# i2c_adc_1.net
KiCad netlist of a schematic drawn in EAGLE
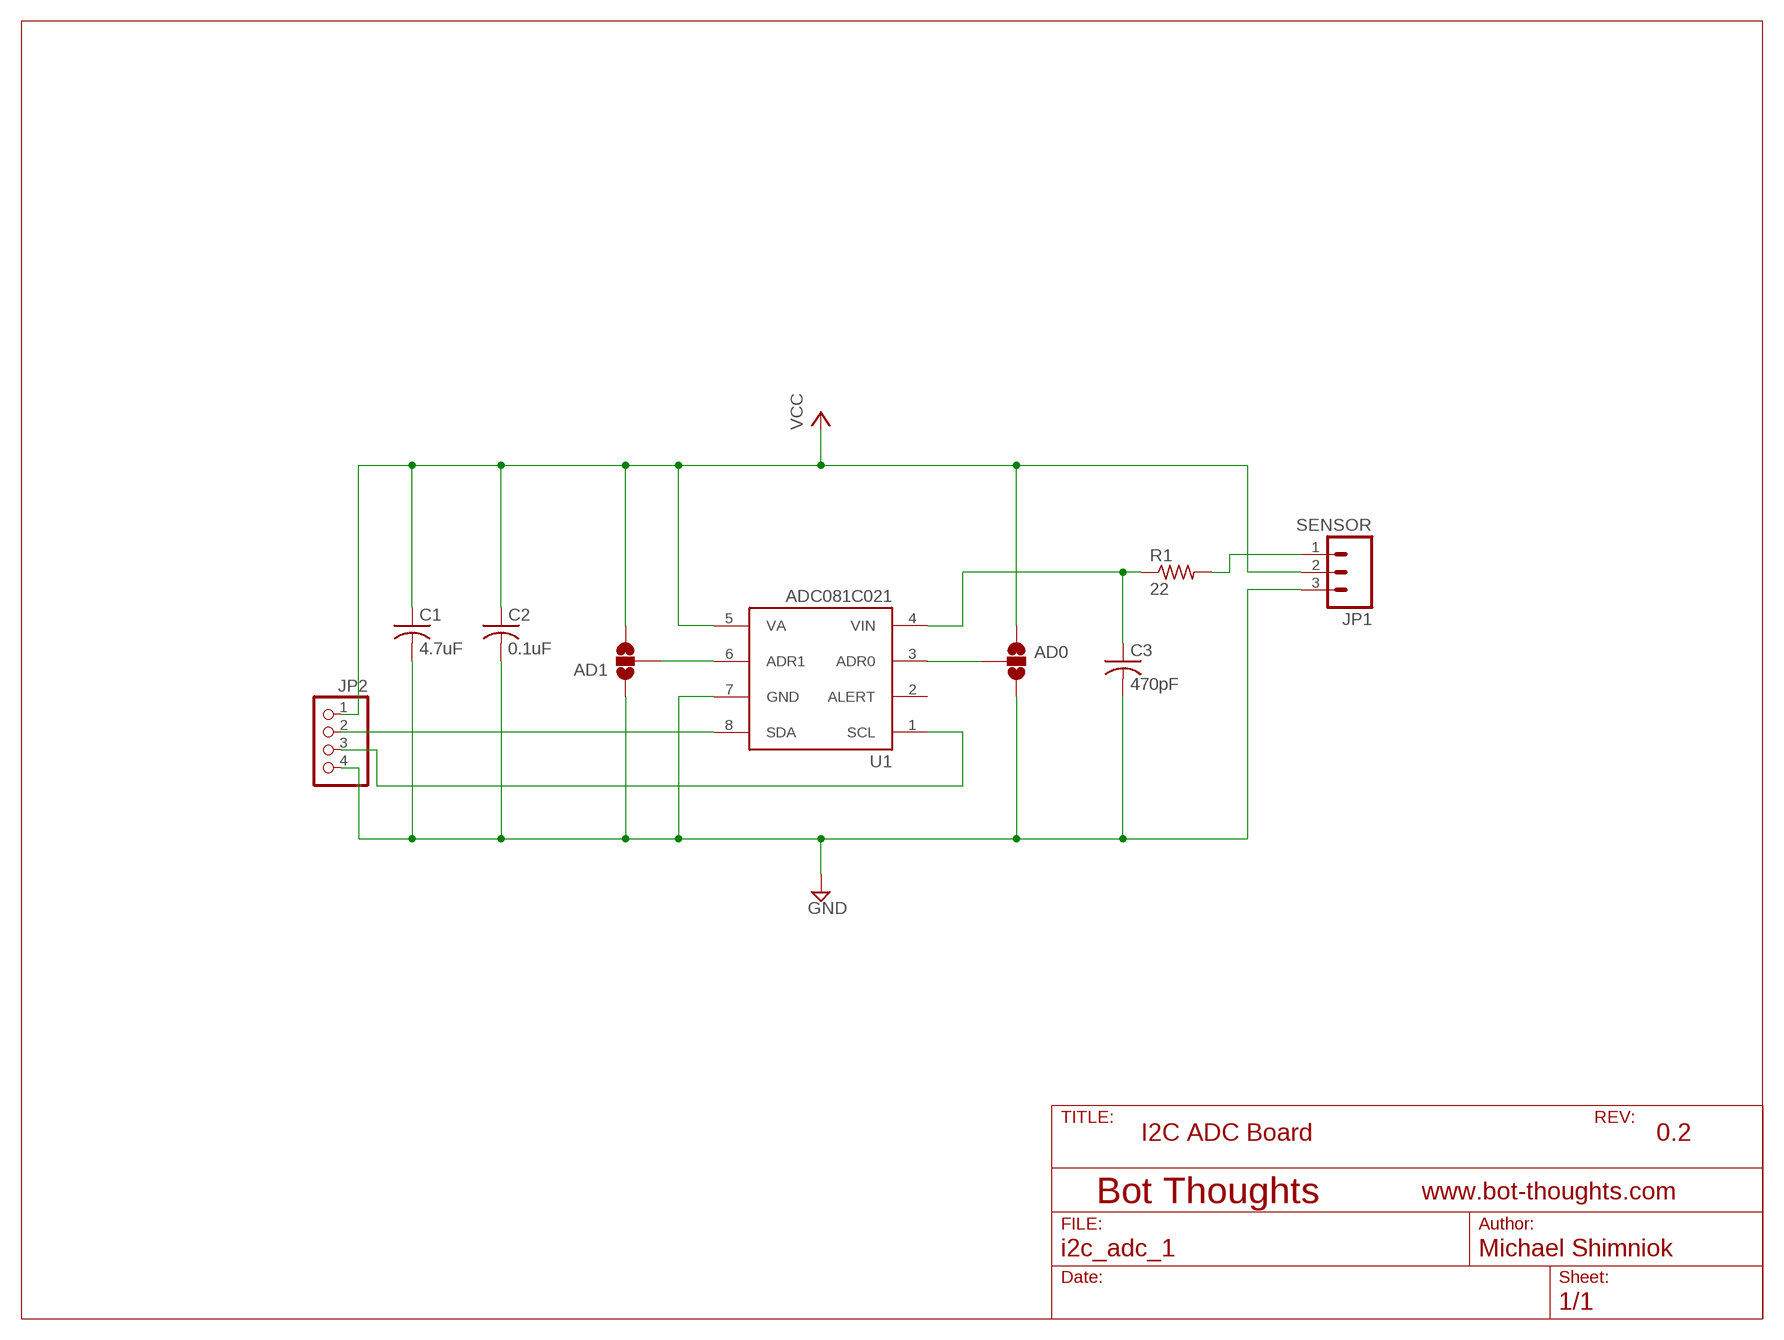
[diagram p0: schematic, sheet 1]

(export (version "E")
  (design (tool "Eeschema 10.0.6"))
  (components
    (comp (ref "AD0")
      (value "SOLDERJUMPER_2WAYS")
      (footprint "eagle-import:SJ_3")
      (libsource (lib "eagle-import") (part "SOLDERJUMPER_2WAYS"))
    )
    (comp (ref "AD1")
      (value "SOLDERJUMPER_2WAYS")
      (footprint "eagle-import:SJ_3")
      (libsource (lib "eagle-import") (part "SOLDERJUMPER_2WAYS"))
    )
    (comp (ref "C1")
      (value "4.7uF")
      (footprint "eagle-import:C0603")
      (libsource (lib "eagle-import") (part "C-USC0603"))
    )
    (comp (ref "C2")
      (value "0.1uF")
      (footprint "eagle-import:C0603")
      (libsource (lib "eagle-import") (part "C-USC0603"))
    )
    (comp (ref "C3")
      (value "470pF")
      (footprint "eagle-import:C0603")
      (libsource (lib "eagle-import") (part "C-USC0603"))
    )
    (comp (ref "JP1")
      (value "SENSOR")
      (footprint "eagle-import:1X03")
      (libsource (lib "eagle-import") (part "M03PTH"))
    )
    (comp (ref "JP2")
      (value "PINHD-1X04_2.54-S")
      (footprint "eagle-import:1X04-S")
      (libsource (lib "eagle-import") (part "PINHD-1X04_2.54-S"))
    )
    (comp (ref "R1")
      (value "22")
      (footprint "eagle-import:R0603")
      (libsource (lib "eagle-import") (part "R-US_R0603"))
    )
    (comp (ref "U1")
      (value "ADC081C021")
      (footprint "eagle-import:MSOP8_0.65")
      (libsource (lib "eagle-import") (part "ADC081C021"))
    )
  )
  (nets
    (net (code "1") (name "GND") (class "Default")
      (node (ref "AD0") (pin "3") (pinfunction "3_3") (pintype "passive"))
      (node (ref "AD1") (pin "1") (pinfunction "1_1") (pintype "passive"))
      (node (ref "C1") (pin "2") (pinfunction "2_2") (pintype "passive"))
      (node (ref "C2") (pin "2") (pinfunction "2_2") (pintype "passive"))
      (node (ref "C3") (pin "2") (pinfunction "2_2") (pintype "passive"))
      (node (ref "JP1") (pin "3") (pinfunction "3_3") (pintype "passive"))
      (node (ref "JP2") (pin "4") (pinfunction "4_4") (pintype "passive"))
      (node (ref "U1") (pin "7") (pinfunction "GND_7") (pintype "bidirectional"))
    )
    (net (code "2") (name "Net-(JP1-Pad1)") (class "Default")
      (node (ref "JP1") (pin "1") (pinfunction "1_1") (pintype "passive"))
      (node (ref "R1") (pin "2") (pinfunction "2_2") (pintype "passive"))
    )
    (net (code "3") (name "Net-(U1-ADR0)") (class "Default")
      (node (ref "AD0") (pin "2") (pinfunction "2_2") (pintype "passive"))
      (node (ref "U1") (pin "3") (pinfunction "ADR0_3") (pintype "bidirectional"))
    )
    (net (code "4") (name "Net-(U1-ADR1)") (class "Default")
      (node (ref "AD1") (pin "2") (pinfunction "2_2") (pintype "passive"))
      (node (ref "U1") (pin "6") (pinfunction "ADR1_6") (pintype "bidirectional"))
    )
    (net (code "5") (name "Net-(U1-SCL)") (class "Default")
      (node (ref "JP2") (pin "3") (pinfunction "3_3") (pintype "passive"))
      (node (ref "U1") (pin "1") (pinfunction "SCL_1") (pintype "bidirectional"))
    )
    (net (code "6") (name "Net-(U1-SDA)") (class "Default")
      (node (ref "JP2") (pin "2") (pinfunction "2_2") (pintype "passive"))
      (node (ref "U1") (pin "8") (pinfunction "SDA_8") (pintype "bidirectional"))
    )
    (net (code "7") (name "Net-(U1-VIN)") (class "Default")
      (node (ref "C3") (pin "1") (pinfunction "1_1") (pintype "passive"))
      (node (ref "R1") (pin "1") (pinfunction "1_1") (pintype "passive"))
      (node (ref "U1") (pin "4") (pinfunction "VIN_4") (pintype "bidirectional"))
    )
    (net (code "8") (name "VCC") (class "Default")
      (node (ref "AD0") (pin "1") (pinfunction "1_1") (pintype "passive"))
      (node (ref "AD1") (pin "3") (pinfunction "3_3") (pintype "passive"))
      (node (ref "C1") (pin "1") (pinfunction "1_1") (pintype "passive"))
      (node (ref "C2") (pin "1") (pinfunction "1_1") (pintype "passive"))
      (node (ref "JP1") (pin "2") (pinfunction "2_2") (pintype "passive"))
      (node (ref "JP2") (pin "1") (pinfunction "1_1") (pintype "passive"))
      (node (ref "U1") (pin "5") (pinfunction "VA_5") (pintype "bidirectional"))
    )
    (net (code "9") (name "unconnected-(U1-ALERT-Pad2)") (class "Default")
      (node (ref "U1") (pin "2") (pinfunction "ALERT_2") (pintype "bidirectional"))
    )
  )
)
